# Transistor_Driver.net
KiCad netlist of a schematic drawn in Altium Designer
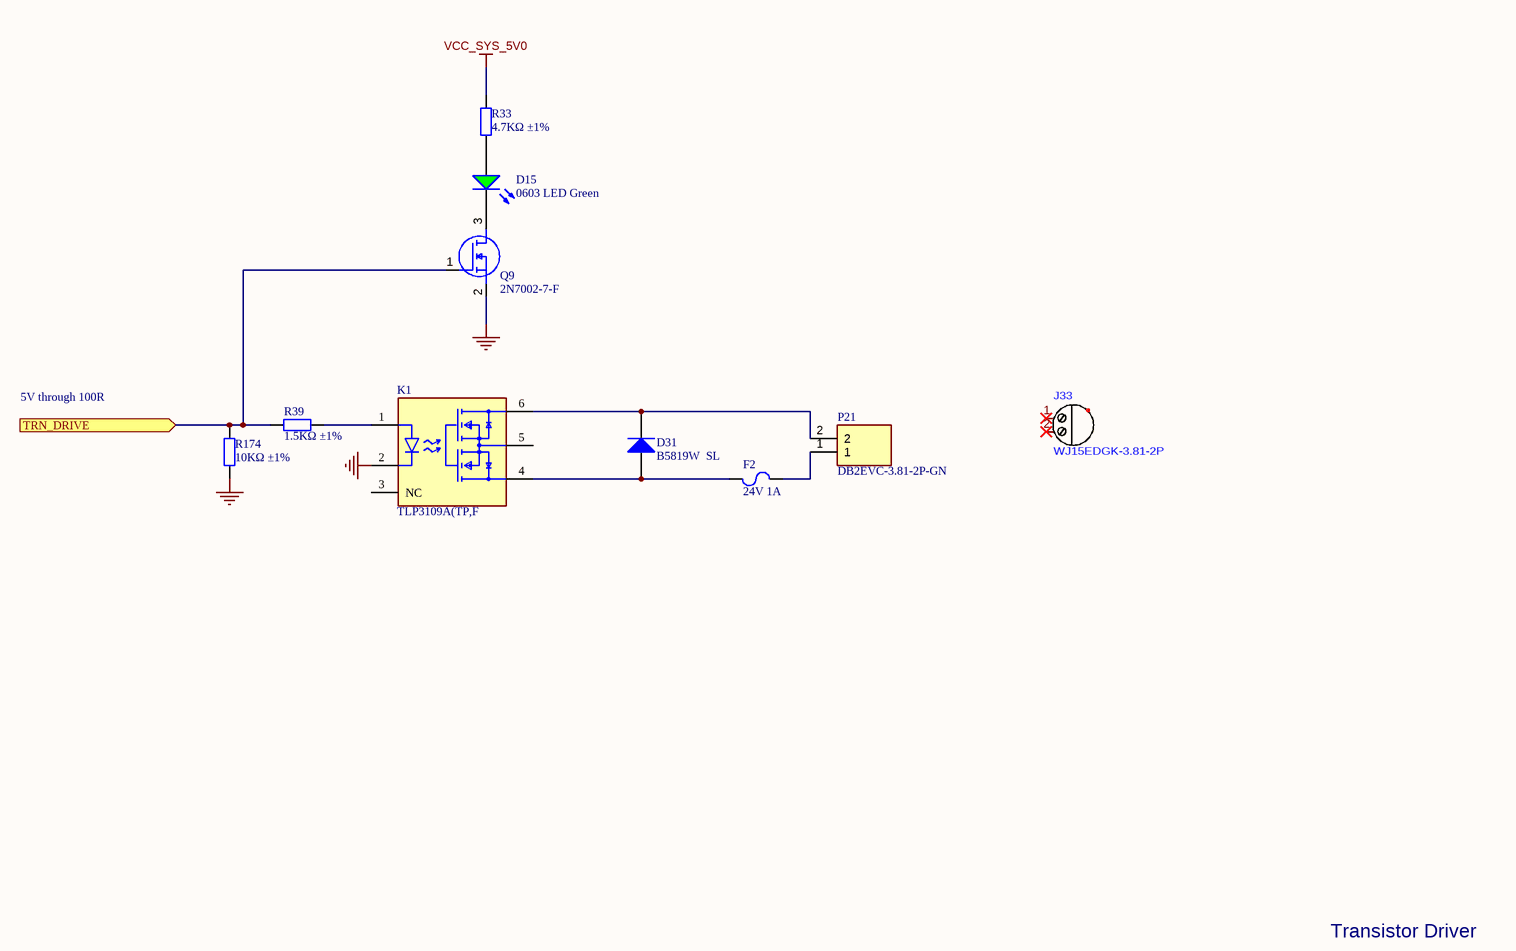
[diagram p0: Transistor_Driver.SchDoc]

(export (version "E")
  (design (tool "Eeschema 10.0.6"))
  (components
    (comp (ref "D15")
      (value "0603 LED Green")
      (footprint "0603_LED_S1 - GREEN")
      (description "20mA -40℃~+85℃ 515nm~530nm Emerald 120° 60mW 0603 Light Emitting Diodes (LED) ROHS")
      (fields (field (name "MANUFACTURER PART NUMBER") "MHT192UGCT") (field (name "MANUFACTURER") "MEIHUA"))
      (libsource (lib "Sienci_Labs") (part "MHT192UGCT"))
    )
    (comp (ref "D31")
      (value "B5819W  SL")
      (footprint "SOD-123")
      (description "40V 600mV@1A 1A SOD-123 Schottky Barrier Diodes (SBD) ROHS")
      (fields
        (field (name "MANUFACTURER PART NUMBER") "B5819W SL")
        (field (name "MANUFACTURER") "Jiangsu Changjing Electronics Technology Co., Ltd.")
      )
      (libsource (lib "Sienci_Labs") (part "B5819W  SL"))
    )
    (comp (ref "F2")
      (value "24V 1A")
      (footprint "1206_C")
      (description "24V 1A 0.1s 1206 PTC Resettable Fuses RoHS")
      (fields
        (field (name "MANUFACTURER") "Jinrui Electronic Materials Co.")
        (field (name "PARTNUMBER") "JK-nSMD050-24")
      )
      (libsource (lib "PrintNC_GRBLHAL_Breakout") (part "JK-nSMD050-24"))
    )
    (comp (ref "J33")
      (value "WJ15EDGK-3.81-2P")
      (description "2 1 3.81mm Green Plug P=3.81mm Pluggable System Terminal Block ROHS")
      (fields (field (name "MANUFACTURER") "Ningbo"))
      (libsource (lib "Sienci_Labs") (part "WJ15EDGK-3.81-2P"))
    )
    (comp (ref "K1")
      (value "TLP3109A(TP,F")
      (footprint "FP-11-7C1S-MFG")
      (description "Relay SSR 10mA 1.8V DC-IN 3A 100V DC-OUT 6-Pin 11-7C1S Emboss T/R")
      (fields (field (name "MANUFACTURER") "Toshiba"))
      (libsource (lib "Sienci_Labs") (part "TLP3109A(TP,F"))
    )
    (comp (ref "P21")
      (value "DB2EVC-3.81-2P-GN")
      (footprint "CONN-TH_5P-P3.81_DB2EVC-3.81-2p")
      (description "3.81mm Green Board Edge/Receptacle-Close Push-Pull,P=3.81mm Pluggable System Terminal Block ROHS")
      (fields (field (name "MANUFACTURER") "DIBO"))
      (libsource (lib "Sienci_Labs") (part "DB2EVC-3.81-2P-GN"))
    )
    (comp (ref "Q9")
      (value "2N7002-7-F")
      (footprint "SOT-23(SOT-23-3)")
      (description "60V 115mA 7.5Ω@5V,50mA 370mW N Channel SOT-23 MOSFETs ROHS")
      (fields (field (name "MANUFACTURER") "Diodes Inc.") (field (name "MOUSER PART NUMBER") "621-2N7002-F"))
      (libsource (lib "Sienci_Labs") (part "2N7002-7-F"))
    )
    (comp (ref "R33")
      (value "4.7KΩ ±1%")
      (footprint "0402_R")
      (description "Chip resistor")
      (fields
        (field (name "MANUFACTURER") "Uniroyal Elec")
        (field (name "MANUFACTURER PART NUMBER") "0402WGF4701TCE")
      )
      (libsource (lib "Sienci_Labs") (part "0402 4.7K (4701) 1%"))
    )
    (comp (ref "R39")
      (value "1.5KΩ ±1%")
      (footprint "0402_R")
      (description "Chip resistor")
      (fields
        (field (name "MANUFACTURER") "Uniroyal Elec")
        (field (name "MANUFACTURER PART NUMBER") "0402WGF1501TCE")
      )
      (libsource (lib "RES") (part "0402 1.5K (1501) 1%"))
    )
    (comp (ref "R174")
      (value "10KΩ ±1%")
      (footprint "0402_R")
      (description "Chip resistor")
      (fields
        (field (name "MANUFACTURER") "Uniroyal Elec")
        (field (name "MANUFACTURER PART NUMBER") "0402WGF1002TCE")
      )
      (libsource (lib "Sienci_Labs") (part "0402 10K (1002) 1%"))
    )
  )
  (nets
    (net (code "1") (name "/TRN_DRIVE") (class "Default")
      (node (ref "Q9") (pin "1") (pinfunction "G_1") (pintype "passive"))
      (node (ref "R174") (pin "2") (pinfunction "2_2") (pintype "passive"))
      (node (ref "R39") (pin "1") (pinfunction "1_1") (pintype "passive"))
    )
    (net (code "2") (name "GND") (class "Default")
      (node (ref "K1") (pin "2") (pinfunction "C_2") (pintype "passive"))
      (node (ref "Q9") (pin "2") (pinfunction "S_2") (pintype "passive"))
      (node (ref "R174") (pin "1") (pinfunction "1_1") (pintype "passive"))
    )
    (net (code "3") (name "Net-(D15-PadA)") (class "Default")
      (node (ref "D15") (pin "A") (pinfunction "A_A") (pintype "passive"))
      (node (ref "R33") (pin "1") (pinfunction "1_1") (pintype "passive"))
    )
    (net (code "4") (name "Net-(D31-A)") (class "Default")
      (node (ref "D31") (pin "1") (pinfunction "A_1") (pintype "passive"))
      (node (ref "F2") (pin "1") (pinfunction "1_1") (pintype "passive"))
      (node (ref "K1") (pin "4") (pinfunction "Drain_4") (pintype "passive"))
    )
    (net (code "5") (name "Net-(D31-K)") (class "Default")
      (node (ref "D31") (pin "2") (pinfunction "K_2") (pintype "passive"))
      (node (ref "K1") (pin "6") (pinfunction "Drain_6") (pintype "passive"))
      (node (ref "P21") (pin "2") (pinfunction "2_2") (pintype "passive"))
    )
    (net (code "6") (name "Net-(F2-Pad2)") (class "Default")
      (node (ref "F2") (pin "2") (pinfunction "2_2") (pintype "passive"))
      (node (ref "P21") (pin "1") (pinfunction "1_1") (pintype "passive"))
    )
    (net (code "7") (name "Net-(K1-A)") (class "Default")
      (node (ref "K1") (pin "1") (pinfunction "A_1") (pintype "passive"))
      (node (ref "R39") (pin "2") (pinfunction "2_2") (pintype "passive"))
    )
    (net (code "8") (name "Net-(Q9-D)") (class "Default")
      (node (ref "D15") (pin "K") (pinfunction "K_K") (pintype "passive"))
      (node (ref "Q9") (pin "3") (pinfunction "D_3") (pintype "passive"))
    )
    (net (code "9") (name "VCC_SYS_5V0") (class "Default")
      (node (ref "R33") (pin "2") (pinfunction "2_2") (pintype "passive"))
    )
    (net (code "10") (name "unconnected-(J33-Pad1)") (class "Default")
      (node (ref "J33") (pin "1") (pinfunction "1_1") (pintype "passive+no_connect"))
    )
    (net (code "11") (name "unconnected-(J33-Pad2)") (class "Default")
      (node (ref "J33") (pin "2") (pinfunction "2_2") (pintype "passive+no_connect"))
    )
    (net (code "12") (name "unconnected-(K1-NC-Pad3)") (class "Default")
      (node (ref "K1") (pin "3") (pinfunction "NC_3") (pintype "passive"))
    )
    (net (code "13") (name "unconnected-(K1-Source-Pad5)") (class "Default")
      (node (ref "K1") (pin "5") (pinfunction "Source_5") (pintype "passive"))
    )
  )
)
